# PaintDuino.net
KiCad netlist of a schematic drawn in EAGLE
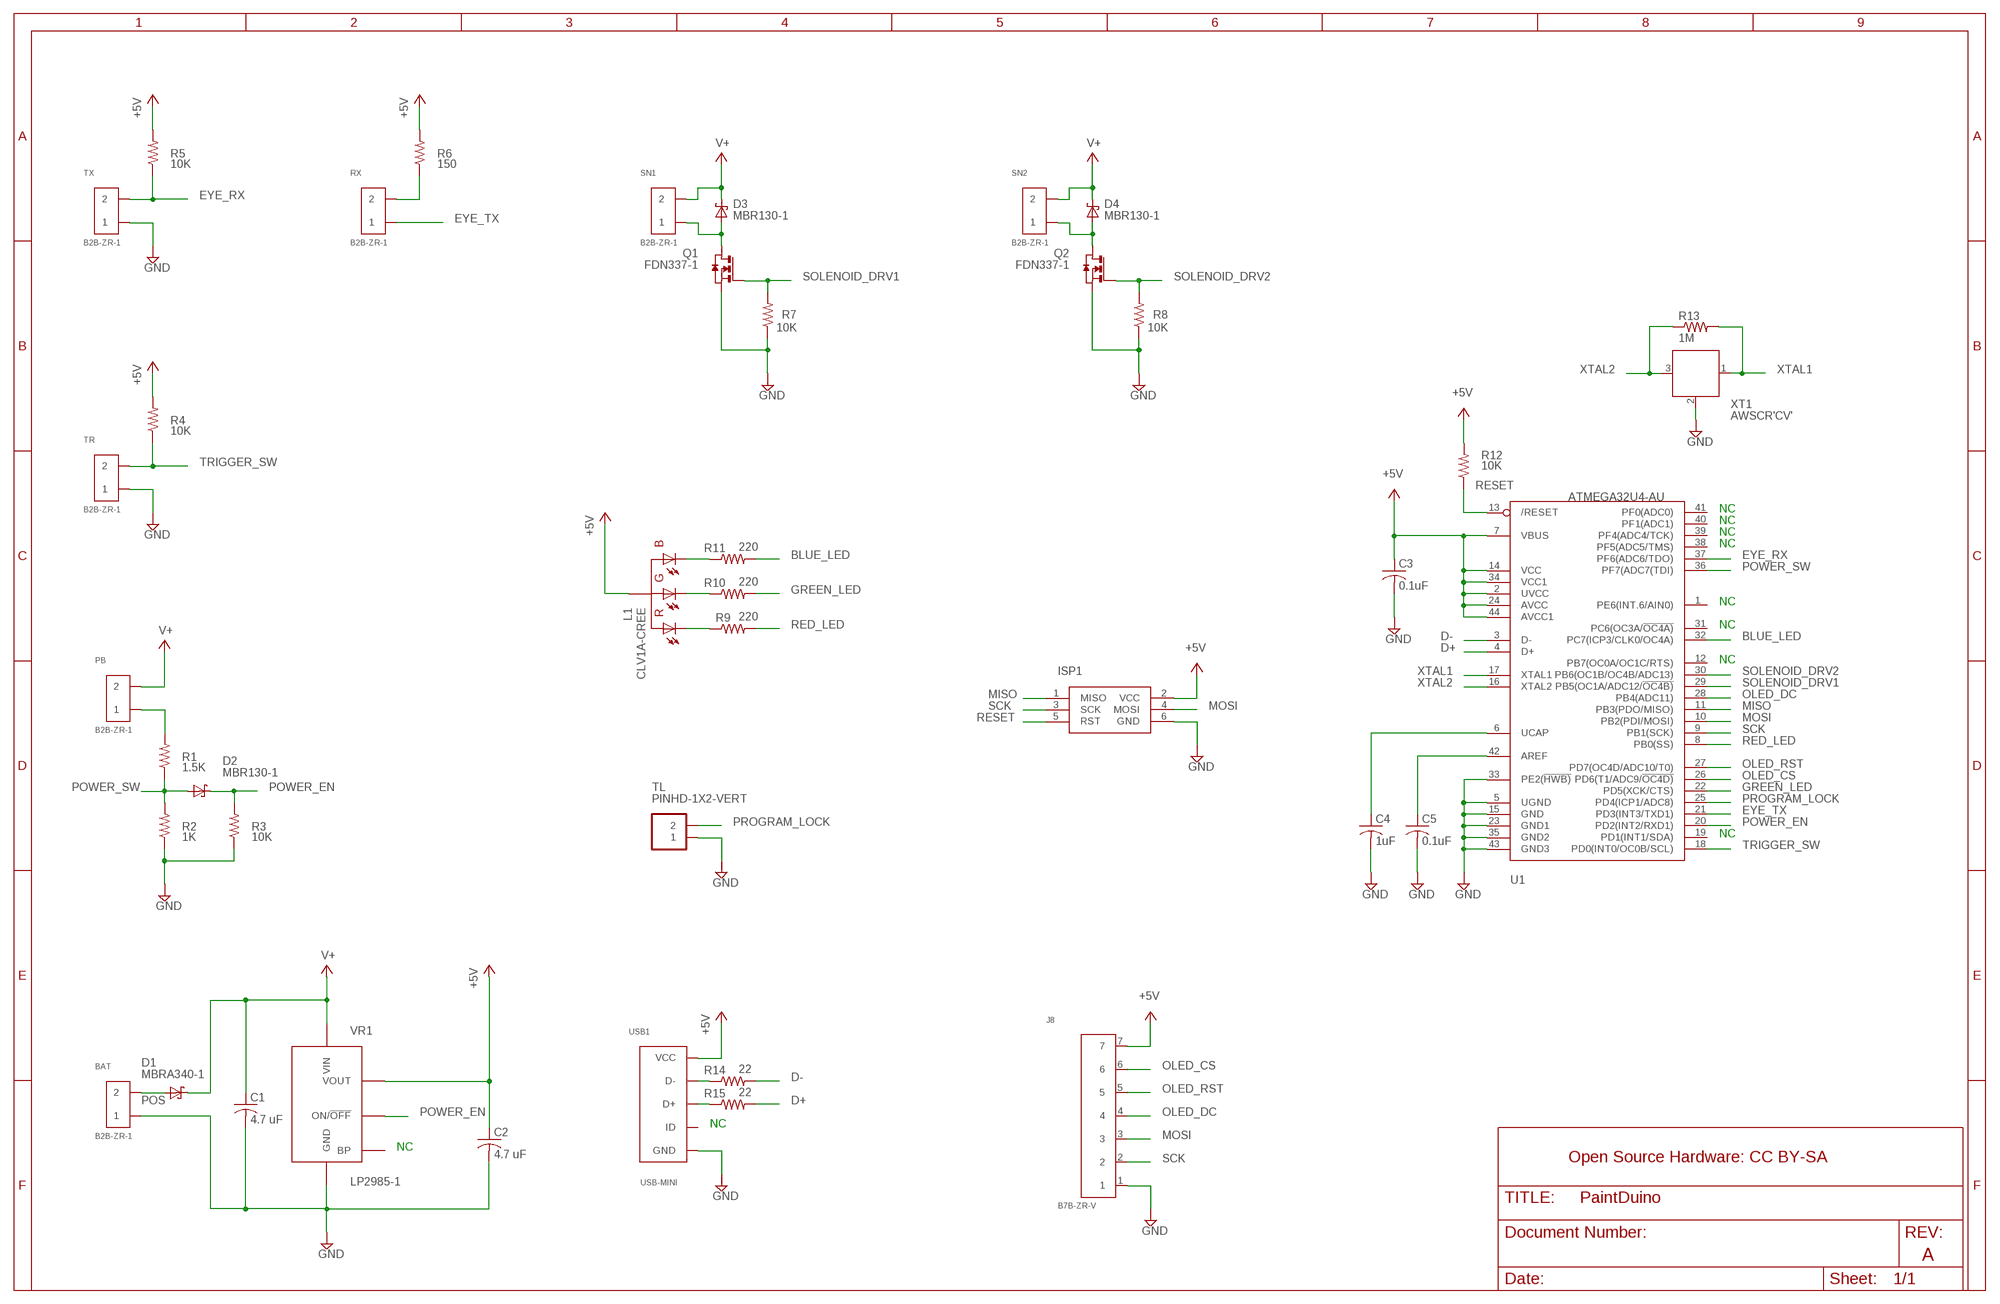
[diagram p0: schematic, sheet 1]

(export (version "E")
  (design (tool "Eeschema 10.0.6"))
  (components
    (comp (ref "BAT")
      (value "B2B-ZR-1")
      (footprint "eagle-import:B2B-ZR")
      (libsource (lib "eagle-import") (part "B2B-ZR-1"))
    )
    (comp (ref "C1")
      (value "4.7 uF")
      (footprint "eagle-import:C0805")
      (libsource (lib "eagle-import") (part "CAP-0805"))
    )
    (comp (ref "C2")
      (value "4.7 uF")
      (footprint "eagle-import:C0805")
      (libsource (lib "eagle-import") (part "CAP-0805"))
    )
    (comp (ref "C3")
      (value "0.1uF")
      (footprint "eagle-import:C0805")
      (libsource (lib "eagle-import") (part "CAP-0805"))
    )
    (comp (ref "C4")
      (value "1uF")
      (footprint "eagle-import:C0805")
      (libsource (lib "eagle-import") (part "CAP-0805"))
    )
    (comp (ref "C5")
      (value "0.1uF")
      (footprint "eagle-import:C0805")
      (libsource (lib "eagle-import") (part "CAP-0805"))
    )
    (comp (ref "D1")
      (value "MBRA340-1")
      (footprint "eagle-import:DO214AC")
      (libsource (lib "eagle-import") (part "MBRA340-1"))
    )
    (comp (ref "D2")
      (value "MBR130-1")
      (footprint "eagle-import:SOD123")
      (libsource (lib "eagle-import") (part "MBR130-1"))
    )
    (comp (ref "D3")
      (value "MBR130-1")
      (footprint "eagle-import:SOD123")
      (libsource (lib "eagle-import") (part "MBR130-1"))
    )
    (comp (ref "D4")
      (value "MBR130-1")
      (footprint "eagle-import:SOD123")
      (libsource (lib "eagle-import") (part "MBR130-1"))
    )
    (comp (ref "ISP1")
      (value "AVRISP-6")
      (footprint "eagle-import:AVRISP")
      (libsource (lib "eagle-import") (part "AVRISP-6"))
    )
    (comp (ref "J8")
      (value "B7B-ZR-V")
      (footprint "eagle-import:B7B-ZR")
      (libsource (lib "eagle-import") (part "B7B-ZR-V"))
    )
    (comp (ref "L1")
      (value "CLV1A-CREE")
      (footprint "eagle-import:PLCC4")
      (libsource (lib "eagle-import") (part "CLV1A-CREE"))
    )
    (comp (ref "PB")
      (value "B2B-ZR-1")
      (footprint "eagle-import:B2B-ZR")
      (libsource (lib "eagle-import") (part "B2B-ZR-1"))
    )
    (comp (ref "Q1")
      (value "FDN337-1")
      (footprint "eagle-import:SOT23")
      (libsource (lib "eagle-import") (part "FDN359-1"))
    )
    (comp (ref "Q2")
      (value "FDN337-1")
      (footprint "eagle-import:SOT23")
      (libsource (lib "eagle-import") (part "FDN359-1"))
    )
    (comp (ref "R1")
      (value "1.5K")
      (footprint "eagle-import:R0805")
      (libsource (lib "eagle-import") (part "RES-2"))
    )
    (comp (ref "R2")
      (value "1K")
      (footprint "eagle-import:R0805")
      (libsource (lib "eagle-import") (part "RES-2"))
    )
    (comp (ref "R3")
      (value "10K")
      (footprint "eagle-import:R0805")
      (libsource (lib "eagle-import") (part "RES-2"))
    )
    (comp (ref "R4")
      (value "10K")
      (footprint "eagle-import:R0805")
      (libsource (lib "eagle-import") (part "RES-2"))
    )
    (comp (ref "R5")
      (value "10K")
      (footprint "eagle-import:R0805")
      (libsource (lib "eagle-import") (part "RES-2"))
    )
    (comp (ref "R6")
      (value "150")
      (footprint "eagle-import:R0805")
      (libsource (lib "eagle-import") (part "RES-2"))
    )
    (comp (ref "R7")
      (value "10K")
      (footprint "eagle-import:R0805")
      (libsource (lib "eagle-import") (part "RES-2"))
    )
    (comp (ref "R8")
      (value "10K")
      (footprint "eagle-import:R0805")
      (libsource (lib "eagle-import") (part "RES-2"))
    )
    (comp (ref "R9")
      (value "220")
      (footprint "eagle-import:R0805")
      (libsource (lib "eagle-import") (part "RES-2"))
    )
    (comp (ref "R10")
      (value "220")
      (footprint "eagle-import:R0805")
      (libsource (lib "eagle-import") (part "RES-2"))
    )
    (comp (ref "R11")
      (value "220")
      (footprint "eagle-import:R0805")
      (libsource (lib "eagle-import") (part "RES-2"))
    )
    (comp (ref "R12")
      (value "10K")
      (footprint "eagle-import:R0805")
      (libsource (lib "eagle-import") (part "RES-2"))
    )
    (comp (ref "R13")
      (value "1M")
      (footprint "eagle-import:R0805")
      (libsource (lib "eagle-import") (part "RES-2"))
    )
    (comp (ref "R14")
      (value "22")
      (footprint "eagle-import:R0805")
      (libsource (lib "eagle-import") (part "RES-2"))
    )
    (comp (ref "R15")
      (value "22")
      (footprint "eagle-import:R0805")
      (libsource (lib "eagle-import") (part "RES-2"))
    )
    (comp (ref "RX")
      (value "B2B-ZR-1")
      (footprint "eagle-import:B2B-ZR")
      (libsource (lib "eagle-import") (part "B2B-ZR-1"))
    )
    (comp (ref "SN1")
      (value "B2B-ZR-1")
      (footprint "eagle-import:B2B-ZR")
      (libsource (lib "eagle-import") (part "B2B-ZR-1"))
    )
    (comp (ref "SN2")
      (value "B2B-ZR-1")
      (footprint "eagle-import:B2B-ZR")
      (libsource (lib "eagle-import") (part "B2B-ZR-1"))
    )
    (comp (ref "TL")
      (value "PINHD-1X2-VERT")
      (footprint "eagle-import:1X02")
      (libsource (lib "eagle-import") (part "PINHD-1X2-VERT"))
    )
    (comp (ref "TR")
      (value "B2B-ZR-1")
      (footprint "eagle-import:B2B-ZR")
      (libsource (lib "eagle-import") (part "B2B-ZR-1"))
    )
    (comp (ref "TX")
      (value "B2B-ZR-1")
      (footprint "eagle-import:B2B-ZR")
      (libsource (lib "eagle-import") (part "B2B-ZR-1"))
    )
    (comp (ref "U1")
      (value "ATMEGA32U4-AU")
      (footprint "eagle-import:TQFP44")
      (libsource (lib "eagle-import") (part "ATMEGA32U4-AU"))
    )
    (comp (ref "USB1")
      (value "USB-MINI")
      (footprint "eagle-import:USB-M2")
      (libsource (lib "eagle-import") (part "USB-MINI"))
    )
    (comp (ref "VR1")
      (value "LP2985-1")
      (footprint "eagle-import:SOT23-5")
      (libsource (lib "eagle-import") (part "LP2985-1"))
    )
    (comp (ref "XT1")
      (value "AWSCR'CV'")
      (footprint "eagle-import:AWSCR-CV")
      (libsource (lib "eagle-import") (part "AWSCR'CV'"))
    )
  )
  (nets
    (net (code "1") (name "+5V") (class "Default")
      (node (ref "C2") (pin "1") (pinfunction "1_1") (pintype "passive"))
      (node (ref "C3") (pin "1") (pinfunction "1_1") (pintype "passive"))
      (node (ref "ISP1") (pin "2") (pinfunction "VCC_2") (pintype "passive"))
      (node (ref "J8") (pin "7") (pinfunction "7_7") (pintype "passive"))
      (node (ref "L1") (pin "2-CA") (pinfunction "A_2-CA") (pintype "passive"))
      (node (ref "R12") (pin "2") (pinfunction "2_2") (pintype "passive"))
      (node (ref "R4") (pin "2") (pinfunction "2_2") (pintype "passive"))
      (node (ref "R5") (pin "2") (pinfunction "2_2") (pintype "passive"))
      (node (ref "R6") (pin "2") (pinfunction "2_2") (pintype "passive"))
      (node (ref "U1") (pin "14") (pinfunction "VCC_14") (pintype "passive"))
      (node (ref "U1") (pin "2") (pinfunction "UVCC_2") (pintype "passive"))
      (node (ref "U1") (pin "24") (pinfunction "AVCC_24") (pintype "passive"))
      (node (ref "U1") (pin "34") (pinfunction "VCC1_34") (pintype "passive"))
      (node (ref "U1") (pin "44") (pinfunction "AVCC1_44") (pintype "passive"))
      (node (ref "U1") (pin "7") (pinfunction "VBUS_7") (pintype "passive"))
      (node (ref "USB1") (pin "1") (pinfunction "VCC_1") (pintype "passive"))
      (node (ref "VR1") (pin "5") (pinfunction "VOUT_5") (pintype "passive"))
    )
    (net (code "2") (name "/BLUE_LED") (class "Default")
      (node (ref "R11") (pin "2") (pinfunction "2_2") (pintype "passive"))
      (node (ref "U1") (pin "32") (pinfunction "PC7(ICP3/CLK0/OC4A)_32") (pintype "passive"))
    )
    (net (code "3") (name "/D+") (class "Default")
      (node (ref "R15") (pin "2") (pinfunction "2_2") (pintype "passive"))
      (node (ref "U1") (pin "4") (pinfunction "D+_4") (pintype "passive"))
    )
    (net (code "4") (name "/D-") (class "Default")
      (node (ref "R14") (pin "2") (pinfunction "2_2") (pintype "passive"))
      (node (ref "U1") (pin "3") (pinfunction "D-_3") (pintype "passive"))
    )
    (net (code "5") (name "/EYE_RX") (class "Default")
      (node (ref "R5") (pin "1") (pinfunction "1_1") (pintype "passive"))
      (node (ref "TX") (pin "2") (pinfunction "2_2") (pintype "passive"))
      (node (ref "U1") (pin "37") (pinfunction "PF6(ADC6/TDO)_37") (pintype "passive"))
    )
    (net (code "6") (name "/EYE_TX") (class "Default")
      (node (ref "RX") (pin "1") (pinfunction "1_1") (pintype "passive"))
      (node (ref "U1") (pin "21") (pinfunction "PD3(INT3/TXD1)_21") (pintype "passive"))
    )
    (net (code "7") (name "/GREEN_LED") (class "Default")
      (node (ref "R10") (pin "2") (pinfunction "2_2") (pintype "passive"))
      (node (ref "U1") (pin "22") (pinfunction "PD5(XCK/CTS)_22") (pintype "passive"))
    )
    (net (code "8") (name "/MISO") (class "Default")
      (node (ref "ISP1") (pin "1") (pinfunction "MISO_1") (pintype "passive"))
      (node (ref "U1") (pin "11") (pinfunction "PB3(PDO/MISO)_11") (pintype "passive"))
    )
    (net (code "9") (name "/MOSI") (class "Default")
      (node (ref "ISP1") (pin "4") (pinfunction "MOSI_4") (pintype "passive"))
      (node (ref "J8") (pin "3") (pinfunction "3_3") (pintype "passive"))
      (node (ref "U1") (pin "10") (pinfunction "PB2(PDI/MOSI)_10") (pintype "passive"))
    )
    (net (code "10") (name "/OLED_CS") (class "Default")
      (node (ref "J8") (pin "6") (pinfunction "6_6") (pintype "passive"))
      (node (ref "U1") (pin "26") (pinfunction "PD6(T1/ADC9/~{OC4D})_26") (pintype "passive"))
    )
    (net (code "11") (name "/OLED_DC") (class "Default")
      (node (ref "J8") (pin "4") (pinfunction "4_4") (pintype "passive"))
      (node (ref "U1") (pin "28") (pinfunction "PB4(ADC11)_28") (pintype "passive"))
    )
    (net (code "12") (name "/OLED_RST") (class "Default")
      (node (ref "J8") (pin "5") (pinfunction "5_5") (pintype "passive"))
      (node (ref "U1") (pin "27") (pinfunction "PD7(OC4D/ADC10/T0)_27") (pintype "passive"))
    )
    (net (code "13") (name "/POS") (class "Default")
      (node (ref "BAT") (pin "2") (pinfunction "2_2") (pintype "passive"))
      (node (ref "D1") (pin "A") (pinfunction "A_A") (pintype "passive"))
    )
    (net (code "14") (name "/POWER_EN") (class "Default")
      (node (ref "D2") (pin "C") (pinfunction "C_C") (pintype "passive"))
      (node (ref "R3") (pin "2") (pinfunction "2_2") (pintype "passive"))
      (node (ref "U1") (pin "20") (pinfunction "PD2(INT2/RXD1)_20") (pintype "passive"))
      (node (ref "VR1") (pin "3") (pinfunction "ON/~{OFF}_3") (pintype "passive"))
    )
    (net (code "15") (name "/POWER_SW") (class "Default")
      (node (ref "D2") (pin "A") (pinfunction "A_A") (pintype "passive"))
      (node (ref "R1") (pin "1") (pinfunction "1_1") (pintype "passive"))
      (node (ref "R2") (pin "2") (pinfunction "2_2") (pintype "passive"))
      (node (ref "U1") (pin "36") (pinfunction "PF7(ADC7(TDI)_36") (pintype "passive"))
    )
    (net (code "16") (name "/PROGRAM_LOCK") (class "Default")
      (node (ref "TL") (pin "2") (pinfunction "2_2") (pintype "passive"))
      (node (ref "U1") (pin "25") (pinfunction "PD4(ICP1/ADC8)_25") (pintype "passive"))
    )
    (net (code "17") (name "/RED_LED") (class "Default")
      (node (ref "R9") (pin "2") (pinfunction "2_2") (pintype "passive"))
      (node (ref "U1") (pin "8") (pinfunction "PB0(SS)_8") (pintype "passive"))
    )
    (net (code "18") (name "/RESET") (class "Default")
      (node (ref "ISP1") (pin "5") (pinfunction "RST_5") (pintype "passive"))
      (node (ref "R12") (pin "1") (pinfunction "1_1") (pintype "passive"))
      (node (ref "U1") (pin "13") (pinfunction "/RESET_13") (pintype "passive"))
    )
    (net (code "19") (name "/SCK") (class "Default")
      (node (ref "ISP1") (pin "3") (pinfunction "SCK_3") (pintype "passive"))
      (node (ref "J8") (pin "2") (pinfunction "2_2") (pintype "passive"))
      (node (ref "U1") (pin "9") (pinfunction "PB1(SCK)_9") (pintype "passive"))
    )
    (net (code "20") (name "/SOLENOID_DRV1") (class "Default")
      (node (ref "Q1") (pin "1") (pinfunction "G_1") (pintype "passive"))
      (node (ref "R7") (pin "2") (pinfunction "2_2") (pintype "passive"))
      (node (ref "U1") (pin "29") (pinfunction "PB5(OC1A/ADC12/~{OC4B})_29") (pintype "passive"))
    )
    (net (code "21") (name "/SOLENOID_DRV2") (class "Default")
      (node (ref "Q2") (pin "1") (pinfunction "G_1") (pintype "passive"))
      (node (ref "R8") (pin "2") (pinfunction "2_2") (pintype "passive"))
      (node (ref "U1") (pin "30") (pinfunction "PB6(OC1B/OC4B/ADC13)_30") (pintype "passive"))
    )
    (net (code "22") (name "/TRIGGER_SW") (class "Default")
      (node (ref "R4") (pin "1") (pinfunction "1_1") (pintype "passive"))
      (node (ref "TR") (pin "2") (pinfunction "2_2") (pintype "passive"))
      (node (ref "U1") (pin "18") (pinfunction "PD0(INT0/OC0B/SCL)_18") (pintype "passive"))
    )
    (net (code "23") (name "/XTAL1") (class "Default")
      (node (ref "R13") (pin "2") (pinfunction "2_2") (pintype "passive"))
      (node (ref "U1") (pin "17") (pinfunction "XTAL1_17") (pintype "passive"))
      (node (ref "XT1") (pin "1") (pinfunction "1_1") (pintype "passive"))
    )
    (net (code "24") (name "/XTAL2") (class "Default")
      (node (ref "R13") (pin "1") (pinfunction "1_1") (pintype "passive"))
      (node (ref "U1") (pin "16") (pinfunction "XTAL2_16") (pintype "passive"))
      (node (ref "XT1") (pin "3") (pinfunction "3_3") (pintype "passive"))
    )
    (net (code "25") (name "GND") (class "Default")
      (node (ref "BAT") (pin "1") (pinfunction "1_1") (pintype "passive"))
      (node (ref "C1") (pin "2") (pinfunction "2_2") (pintype "passive"))
      (node (ref "C2") (pin "2") (pinfunction "2_2") (pintype "passive"))
      (node (ref "C3") (pin "2") (pinfunction "2_2") (pintype "passive"))
      (node (ref "C4") (pin "2") (pinfunction "2_2") (pintype "passive"))
      (node (ref "C5") (pin "2") (pinfunction "2_2") (pintype "passive"))
      (node (ref "ISP1") (pin "6") (pinfunction "GND_6") (pintype "passive"))
      (node (ref "J8") (pin "1") (pinfunction "1_1") (pintype "passive"))
      (node (ref "Q1") (pin "2") (pinfunction "S_2") (pintype "passive"))
      (node (ref "Q2") (pin "2") (pinfunction "S_2") (pintype "passive"))
      (node (ref "R2") (pin "1") (pinfunction "1_1") (pintype "passive"))
      (node (ref "R3") (pin "1") (pinfunction "1_1") (pintype "passive"))
      (node (ref "R7") (pin "1") (pinfunction "1_1") (pintype "passive"))
      (node (ref "R8") (pin "1") (pinfunction "1_1") (pintype "passive"))
      (node (ref "TL") (pin "1") (pinfunction "1_1") (pintype "passive"))
      (node (ref "TR") (pin "1") (pinfunction "1_1") (pintype "passive"))
      (node (ref "TX") (pin "1") (pinfunction "1_1") (pintype "passive"))
      (node (ref "U1") (pin "15") (pinfunction "GND_15") (pintype "passive"))
      (node (ref "U1") (pin "23") (pinfunction "GND1_23") (pintype "passive"))
      (node (ref "U1") (pin "33") (pinfunction "PE2(~{HWB})_33") (pintype "passive"))
      (node (ref "U1") (pin "35") (pinfunction "GND2_35") (pintype "passive"))
      (node (ref "U1") (pin "43") (pinfunction "GND3_43") (pintype "passive"))
      (node (ref "U1") (pin "5") (pinfunction "UGND_5") (pintype "passive"))
      (node (ref "USB1") (pin "5") (pinfunction "GND_5") (pintype "passive"))
      (node (ref "VR1") (pin "2") (pinfunction "GND_2") (pintype "passive"))
      (node (ref "XT1") (pin "2") (pinfunction "2_2") (pintype "passive"))
    )
    (net (code "26") (name "Net-(L1-BC)") (class "Default")
      (node (ref "L1") (pin "3-B") (pinfunction "BC_3-B") (pintype "passive"))
      (node (ref "R11") (pin "1") (pinfunction "1_1") (pintype "passive"))
    )
    (net (code "27") (name "Net-(L1-GC)") (class "Default")
      (node (ref "L1") (pin "4-G") (pinfunction "GC_4-G") (pintype "passive"))
      (node (ref "R10") (pin "1") (pinfunction "1_1") (pintype "passive"))
    )
    (net (code "28") (name "Net-(L1-RC)") (class "Default")
      (node (ref "L1") (pin "1-R") (pinfunction "RC_1-R") (pintype "passive"))
      (node (ref "R9") (pin "1") (pinfunction "1_1") (pintype "passive"))
    )
    (net (code "29") (name "Net-(PB-Pad1)") (class "Default")
      (node (ref "PB") (pin "1") (pinfunction "1_1") (pintype "passive"))
      (node (ref "R1") (pin "2") (pinfunction "2_2") (pintype "passive"))
    )
    (net (code "30") (name "Net-(Q1-D)") (class "Default")
      (node (ref "D3") (pin "A") (pinfunction "A_A") (pintype "passive"))
      (node (ref "Q1") (pin "3") (pinfunction "D_3") (pintype "passive"))
      (node (ref "SN1") (pin "1") (pinfunction "1_1") (pintype "passive"))
    )
    (net (code "31") (name "Net-(Q2-D)") (class "Default")
      (node (ref "D4") (pin "A") (pinfunction "A_A") (pintype "passive"))
      (node (ref "Q2") (pin "3") (pinfunction "D_3") (pintype "passive"))
      (node (ref "SN2") (pin "1") (pinfunction "1_1") (pintype "passive"))
    )
    (net (code "32") (name "Net-(R6-Pad1)") (class "Default")
      (node (ref "R6") (pin "1") (pinfunction "1_1") (pintype "passive"))
      (node (ref "RX") (pin "2") (pinfunction "2_2") (pintype "passive"))
    )
    (net (code "33") (name "Net-(U1-AREF)") (class "Default")
      (node (ref "C5") (pin "1") (pinfunction "1_1") (pintype "passive"))
      (node (ref "U1") (pin "42") (pinfunction "AREF_42") (pintype "passive"))
    )
    (net (code "34") (name "Net-(U1-UCAP)") (class "Default")
      (node (ref "C4") (pin "1") (pinfunction "1_1") (pintype "passive"))
      (node (ref "U1") (pin "6") (pinfunction "UCAP_6") (pintype "passive"))
    )
    (net (code "35") (name "Net-(USB1-D+)") (class "Default")
      (node (ref "R15") (pin "1") (pinfunction "1_1") (pintype "passive"))
      (node (ref "USB1") (pin "3") (pinfunction "D+_3") (pintype "passive"))
    )
    (net (code "36") (name "Net-(USB1-D-)") (class "Default")
      (node (ref "R14") (pin "1") (pinfunction "1_1") (pintype "passive"))
      (node (ref "USB1") (pin "2") (pinfunction "D-_2") (pintype "passive"))
    )
    (net (code "37") (name "V+") (class "Default")
      (node (ref "C1") (pin "1") (pinfunction "1_1") (pintype "passive"))
      (node (ref "D1") (pin "C") (pinfunction "C_C") (pintype "passive"))
      (node (ref "D3") (pin "C") (pinfunction "C_C") (pintype "passive"))
      (node (ref "D4") (pin "C") (pinfunction "C_C") (pintype "passive"))
      (node (ref "PB") (pin "2") (pinfunction "2_2") (pintype "passive"))
      (node (ref "SN1") (pin "2") (pinfunction "2_2") (pintype "passive"))
      (node (ref "SN2") (pin "2") (pinfunction "2_2") (pintype "passive"))
      (node (ref "VR1") (pin "1") (pinfunction "VIN_1") (pintype "passive"))
    )
    (net (code "38") (name "unconnected-(U1-PB7(OC0A{slash}OC1C{slash}RTS)-Pad12)") (class "Default")
      (node (ref "U1") (pin "12") (pinfunction "PB7(OC0A/OC1C/RTS)_12") (pintype "passive"))
    )
    (net (code "39") (name "unconnected-(U1-PC6(OC3A{slash}~{OC4A})-Pad31)") (class "Default")
      (node (ref "U1") (pin "31") (pinfunction "PC6(OC3A/~{OC4A})_31") (pintype "passive"))
    )
    (net (code "40") (name "unconnected-(U1-PD1(INT1{slash}SDA)-Pad19)") (class "Default")
      (node (ref "U1") (pin "19") (pinfunction "PD1(INT1/SDA)_19") (pintype "passive"))
    )
    (net (code "41") (name "unconnected-(U1-PE6(INT.6{slash}AIN0)-Pad1)") (class "Default")
      (node (ref "U1") (pin "1") (pinfunction "PE6(INT.6/AIN0)_1") (pintype "passive"))
    )
    (net (code "42") (name "unconnected-(U1-PF0(ADC0)-Pad41)") (class "Default")
      (node (ref "U1") (pin "41") (pinfunction "PF0(ADC0)_41") (pintype "passive"))
    )
    (net (code "43") (name "unconnected-(U1-PF1(ADC1)-Pad40)") (class "Default")
      (node (ref "U1") (pin "40") (pinfunction "PF1(ADC1)_40") (pintype "passive"))
    )
    (net (code "44") (name "unconnected-(U1-PF4(ADC4{slash}TCK)-Pad39)") (class "Default")
      (node (ref "U1") (pin "39") (pinfunction "PF4(ADC4/TCK)_39") (pintype "passive"))
    )
    (net (code "45") (name "unconnected-(U1-PF5(ADC5{slash}TMS)-Pad38)") (class "Default")
      (node (ref "U1") (pin "38") (pinfunction "PF5(ADC5/TMS)_38") (pintype "passive"))
    )
    (net (code "46") (name "unconnected-(USB1-ID-Pad4)") (class "Default")
      (node (ref "USB1") (pin "4") (pinfunction "ID_4") (pintype "passive"))
    )
    (net (code "47") (name "unconnected-(VR1-BP-Pad4)") (class "Default")
      (node (ref "VR1") (pin "4") (pinfunction "BP_4") (pintype "passive"))
    )
  )
)
